# 5_Power_DWIN.net
KiCad netlist of a schematic drawn in Altium Designer
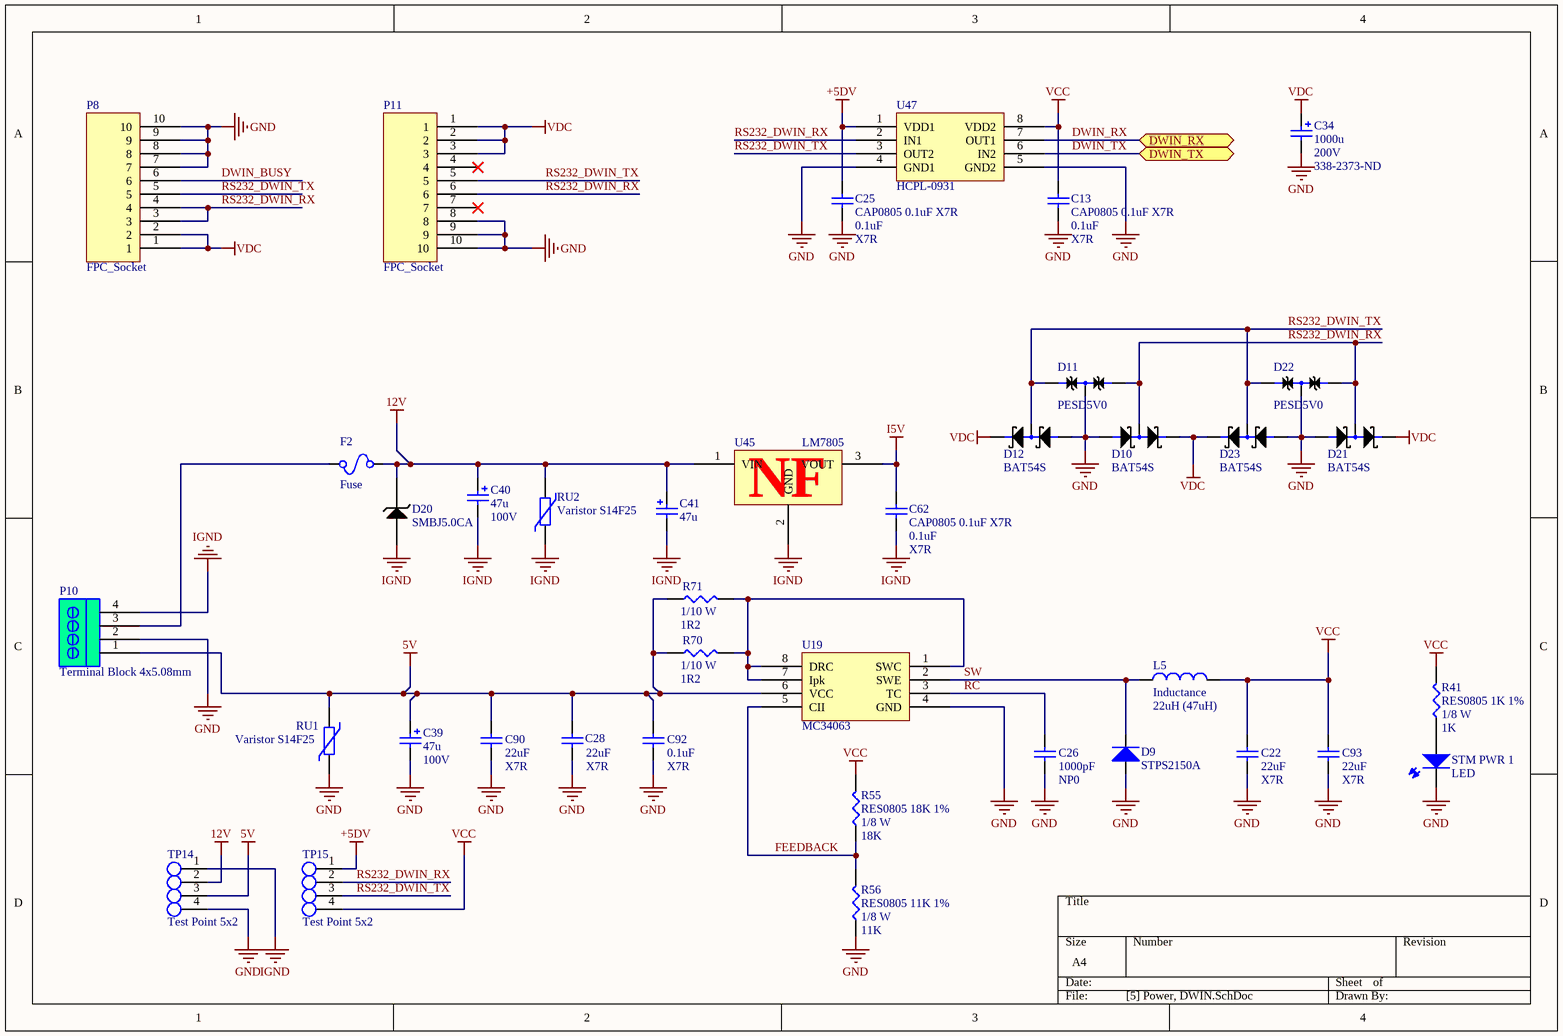
[diagram p0: [5] Power, DWIN.SchDoc]

(export (version "E")
  (design (tool "Eeschema 10.0.6"))
  (components
    (comp (ref "C13")
      (value "CAP0805 0.1uF X7R")
      (footprint "CAP0805")
      (description "Surface-mount ceramic multilayer capacitor")
      (fields
        (field (name "VOLTAGE") "50V")
        (field (name "TOLERANCE") "5%")
        (field (name "ALTIUM_VALUE") "0.1uF")
        (field (name "TYPE") "X7R")
      )
      (libsource (lib "Capacitors") (part "CAP0805 0.1uF X7R"))
    )
    (comp (ref "C22")
      (value "22uF")
      (footprint "CAP1210")
      (description "Surface-mount ceramic multilayer capacitor")
      (fields (field (name "VOLTAGE") "25V") (field (name "TOLERANCE") "10%") (field (name "TYPE") "X7R"))
      (libsource (lib "Capacitors") (part "ChipCap 22uF X7R"))
    )
    (comp (ref "C25")
      (value "CAP0805 0.1uF X7R")
      (footprint "CAP0805")
      (description "Surface-mount ceramic multilayer capacitor")
      (fields
        (field (name "VOLTAGE") "50V")
        (field (name "TOLERANCE") "5%")
        (field (name "ALTIUM_VALUE") "0.1uF")
        (field (name "TYPE") "X7R")
      )
      (libsource (lib "Capacitors") (part "CAP0805 0.1uF X7R"))
    )
    (comp (ref "C26")
      (value "1000pF")
      (footprint "CAP0805")
      (description "Surface-mount ceramic multilayer capacitor")
      (fields (field (name "VOLTAGE") "50V") (field (name "TOLERANCE") "5%") (field (name "TYPE") "NP0"))
      (libsource (lib "Capacitors") (part "CAP0805 1000pF NP0"))
    )
    (comp (ref "C28")
      (value "22uF")
      (footprint "CAP1210")
      (description "Surface-mount ceramic multilayer capacitor")
      (fields (field (name "VOLTAGE") "25V") (field (name "TOLERANCE") "10%") (field (name "TYPE") "X7R"))
      (libsource (lib "Capacitors") (part "ChipCap 22uF X7R"))
    )
    (comp (ref "C34")
      (value "1000u")
      (footprint "CAPPR7.5-16x25_1")
      (description "Polarized Capacitor (Radial)")
      (fields
        (field (name "VOLTAGE") "200V")
        (field (name "SUPPLIER PART NUMBER 1") "338-2373-ND")
        (field (name "Comment") "Cap Pol 200/100")
      )
      (libsource (lib "Common Devices") (part "Cap Pol 200/100"))
    )
    (comp (ref "C39")
      (value "47u")
      (footprint "CAPPR5-10x17_1")
      (description "Polarized Capacitor (Radial)")
      (fields (field (name "VOLTAGE") "100V") (field (name "Comment") "Cap Pol 100/47"))
      (libsource (lib "Common Devices") (part "Cap Pol 100/47"))
    )
    (comp (ref "C40")
      (value "47u")
      (footprint "CAPPR5-10x17_1")
      (description "Polarized Capacitor (Radial)")
      (fields (field (name "VOLTAGE") "100V") (field (name "Comment") "Cap Pol 100/47"))
      (libsource (lib "Common Devices") (part "Cap Pol 100/47"))
    )
    (comp (ref "C41")
      (value "47u")
      (footprint "CAPC7343")
      (description "Polarized Capacitor (Radial)")
      (fields (field (name "Comment") "Cap Pol SMD"))
      (libsource (lib "Common Devices") (part "Cap Pol Chip"))
    )
    (comp (ref "C62")
      (value "CAP0805 0.1uF X7R")
      (footprint "CAP0805")
      (description "Surface-mount ceramic multilayer capacitor")
      (fields
        (field (name "VOLTAGE") "50V")
        (field (name "TOLERANCE") "5%")
        (field (name "ALTIUM_VALUE") "0.1uF")
        (field (name "TYPE") "X7R")
      )
      (libsource (lib "Capacitors") (part "CAP0805 0.1uF X7R"))
    )
    (comp (ref "C90")
      (value "22uF")
      (footprint "CAP1210")
      (description "Surface-mount ceramic multilayer capacitor")
      (fields (field (name "VOLTAGE") "25V") (field (name "TOLERANCE") "10%") (field (name "TYPE") "X7R"))
      (libsource (lib "Capacitors") (part "ChipCap 22uF X7R"))
    )
    (comp (ref "C92")
      (value "0.1uF")
      (footprint "CAP0603")
      (description "Surface-mount ceramic multilayer capacitor")
      (fields (field (name "VOLTAGE") "100V") (field (name "TOLERANCE") "10%") (field (name "TYPE") "X7R"))
      (libsource (lib "Capacitors") (part "ChipCap 0.1uF X7R"))
    )
    (comp (ref "C93")
      (value "22uF")
      (footprint "CAP1210")
      (description "Surface-mount ceramic multilayer capacitor")
      (fields (field (name "VOLTAGE") "25V") (field (name "TOLERANCE") "10%") (field (name "TYPE") "X7R"))
      (libsource (lib "Capacitors") (part "ChipCap 22uF X7R"))
    )
    (comp (ref "D9")
      (value "STPS2150A")
      (footprint "DO-214AS")
      (description "Schottky diode")
      (fields (field (name "VOLTAGE") "150V") (field (name "MANUFACTURER") "ST"))
      (libsource (lib "Common Devices") (part "STPS2150A"))
    )
    (comp (ref "D10")
      (value "BAT54S")
      (footprint "SOT23")
      (description "Small signal schottky dual diode")
      (fields (field (name "MANUFACTURER PART NUMBER") "BAT54S-V-GS08") (field (name "VOLTAGE") "30"))
      (libsource (lib "") (part "BAT54S_1"))
    )
    (comp (ref "D11")
      (value "PESD5V0")
      (footprint "SOT23")
      (description "Low capacitance bidirectional double ESD protection diode")
      (fields (field (name "MANUFACTURER PART NUMBER") "PESD5V0S2BT.215") (field (name "VOLTAGE") "5V"))
      (libsource (lib "Protection") (part "PESD5V0"))
    )
    (comp (ref "D12")
      (value "BAT54S")
      (footprint "SOT23")
      (description "Small signal schottky dual diode")
      (fields (field (name "MANUFACTURER PART NUMBER") "BAT54S-V-GS08") (field (name "VOLTAGE") "30"))
      (libsource (lib "Protection") (part "BAT54S"))
    )
    (comp (ref "D20")
      (value "SMBJ5.0CA")
      (footprint "DO-214AS")
      (description "Transient Voltage Suppressor 600W uni-directional")
      (fields (field (name "VOLTAGE") "5.0V"))
      (libsource (lib "Protection") (part "SMBJ5.0CA"))
    )
    (comp (ref "D21")
      (value "BAT54S")
      (footprint "SOT23")
      (description "Small signal schottky dual diode")
      (fields (field (name "MANUFACTURER PART NUMBER") "BAT54S-V-GS08") (field (name "VOLTAGE") "30"))
      (libsource (lib "") (part "BAT54S_1"))
    )
    (comp (ref "D22")
      (value "PESD5V0")
      (footprint "SOT23")
      (description "Low capacitance bidirectional double ESD protection diode")
      (fields (field (name "MANUFACTURER PART NUMBER") "PESD5V0S2BT.215") (field (name "VOLTAGE") "5V"))
      (libsource (lib "Protection") (part "PESD5V0"))
    )
    (comp (ref "D23")
      (value "BAT54S")
      (footprint "SOT23")
      (description "Small signal schottky dual diode")
      (fields (field (name "MANUFACTURER PART NUMBER") "BAT54S-V-GS08") (field (name "VOLTAGE") "30"))
      (libsource (lib "Protection") (part "BAT54S"))
    )
    (comp (ref "F2")
      (value "Fuse")
      (footprint "PTC1812")
      (description "Fuse PTC 1812 Thermoresistor")
      (libsource (lib "Protection") (part "Fuse PTC1812"))
    )
    (comp (ref "L5")
      (value "Inductance")
      (footprint "IHPL-3232")
      (fields (field (name "ALTIUM_VALUE") "22uH (47uH)"))
      (libsource (lib "Common Devices") (part "ChipInductance"))
    )
    (comp (ref "P8")
      (value "FPC_Socket")
      (footprint "MOLEX Header 8 2mm Pitch")
      (libsource (lib "") (part "FPC_Socket_1"))
    )
    (comp (ref "P10")
      (value "Terminal Block 4x5.08mm")
      (footprint "Socket 4x5.08")
      (description "Terminal Block Socket Right Angle 4x5.08mm 2-Wall")
      (libsource (lib "IndustrialConnectors") (part "Socket_4x5.08_RA_2Wall"))
    )
    (comp (ref "P11")
      (value "FPC_Socket")
      (footprint "Molex FPC/FFC 10pin")
      (libsource (lib "RibbonConnectors") (part "FPC_Socket"))
    )
    (comp (ref "R41")
      (value "RES0805 1K 1%")
      (footprint "RES0805")
      (description "Think Film Chip resistor")
      (fields
        (field (name "TOLERANCE") "1%")
        (field (name "MANUFACTURER PART NUMBER") "RC0805FR-071KL")
        (field (name "RATING") "1/8 W")
        (field (name "ALTIUM_VALUE") "1K")
      )
      (libsource (lib "Resistors") (part "RES0805 1K 1%"))
    )
    (comp (ref "R55")
      (value "RES0805 18K 1%")
      (footprint "RES0805")
      (description "Think Film Chip resistor")
      (fields
        (field (name "TOLERANCE") "1%")
        (field (name "MANUFACTURER PART NUMBER") "RC0805FR-0718KL")
        (field (name "RATING") "1/8 W")
        (field (name "ALTIUM_VALUE") "18K")
      )
      (libsource (lib "Resistors") (part "RES0805 18K 1%"))
    )
    (comp (ref "R56")
      (value "RES0805 11K 1%")
      (footprint "RES0805")
      (description "Think Film Chip resistor")
      (fields
        (field (name "TOLERANCE") "1%")
        (field (name "MANUFACTURER PART NUMBER") "RC0805FR-0711KL")
        (field (name "RATING") "1/8 W")
        (field (name "ALTIUM_VALUE") "11K")
      )
      (libsource (lib "Resistors") (part "RES0805 11K 1%"))
    )
    (comp (ref "R70")
      (value "1R2")
      (footprint "RES1206")
      (description "Think Film Chip resistor")
      (fields
        (field (name "TOLERANCE") "1%")
        (field (name "RATING") "1/10 W")
        (field (name "Comment") "ChipRes 1R2 1%")
      )
      (libsource (lib "Resistors") (part "ChipRes 1R2 1%"))
    )
    (comp (ref "R71")
      (value "1R2")
      (footprint "RES1206")
      (description "Think Film Chip resistor")
      (fields
        (field (name "TOLERANCE") "1%")
        (field (name "RATING") "1/10 W")
        (field (name "Comment") "ChipRes 1R2 1%")
      )
      (libsource (lib "Resistors") (part "ChipRes 1R2 1%"))
    )
    (comp (ref "RU1")
      (value "Varistor S14F25")
      (footprint "S14K25")
      (description "varistor")
      (libsource (lib "Protection") (part "Varistor S14K25"))
    )
    (comp (ref "RU2")
      (value "Varistor S14F25")
      (footprint "S14K25")
      (description "varistor")
      (libsource (lib "Protection") (part "Varistor S14K25"))
    )
    (comp (ref "STM PWR 1") (value "LED") (footprint "PLCC-2") (libsource (lib "LEDs") (part "LED0603")))
    (comp (ref "TP14")
      (value "Test Point 5x2")
      (footprint "PG-1.5-13.5-4P-2.54PH")
      (libsource (lib "Connectors") (part "PG-1.5-13.5-4P-2.54PH"))
    )
    (comp (ref "TP15")
      (value "Test Point 5x2")
      (footprint "PG-1.5-13.5-4P-2.54PH")
      (libsource (lib "Connectors") (part "PG-1.5-13.5-4P-2.54PH"))
    )
    (comp (ref "U19")
      (value "MC34063")
      (footprint "SOP8")
      (description "DC/DC converter control circuit")
      (libsource (lib "ST ARM32") (part "MC34063"))
    )
    (comp (ref "U45")
      (value "LM7805")
      (footprint "TO-220")
      (description "Linear voltage regulator 1A")
      (libsource (lib "Fairchild") (part "LM7805"))
    )
    (comp (ref "U47")
      (value "HCPL-0931")
      (footprint "SOIC8")
      (description "2-bit bi-direction optoisolated buffer")
      (libsource (lib "AVAGO bi-direction optoisolated buffer") (part "HCPL-0931-000E"))
    )
  )
  (nets
    (net (code "1") (name "+5DV") (class "Default")
      (node (ref "C25") (pin "2") (pinfunction "2_2") (pintype "passive"))
      (node (ref "TP15") (pin "1") (pinfunction "1_1") (pintype "passive"))
      (node (ref "U47") (pin "1") (pinfunction "VDD1_1") (pintype "passive"))
    )
    (net (code "2") (name "/DWIN_BUSY") (class "Default")
      (node (ref "P8") (pin "6") (pinfunction "6_6") (pintype "passive"))
    )
    (net (code "3") (name "/DWIN_RX") (class "Default")
      (node (ref "U47") (pin "7") (pinfunction "OUT1_7") (pintype "passive"))
    )
    (net (code "4") (name "/DWIN_TX") (class "Default")
      (node (ref "U47") (pin "6") (pinfunction "IN2_6") (pintype "passive"))
    )
    (net (code "5") (name "/FEEDBACK") (class "Default")
      (node (ref "R55") (pin "1") (pintype "passive"))
      (node (ref "R56") (pin "2") (pintype "passive"))
      (node (ref "U19") (pin "5") (pinfunction "CII_5") (pintype "passive"))
    )
    (net (code "6") (name "/RC") (class "Default")
      (node (ref "C26") (pin "2") (pinfunction "2_2") (pintype "passive"))
      (node (ref "U19") (pin "3") (pinfunction "TC_3") (pintype "passive"))
    )
    (net (code "7") (name "/RS232_DWIN_RX") (class "Default")
      (node (ref "D10") (pin "3") (pinfunction "3_3") (pintype "passive"))
      (node (ref "D11") (pin "2") (pinfunction "2_2") (pintype "passive"))
      (node (ref "D21") (pin "3") (pinfunction "3_3") (pintype "passive"))
      (node (ref "D22") (pin "2") (pinfunction "2_2") (pintype "passive"))
      (node (ref "P11") (pin "6") (pinfunction "6_6") (pintype "passive"))
      (node (ref "P8") (pin "3") (pinfunction "3_3") (pintype "passive"))
      (node (ref "P8") (pin "4") (pinfunction "4_4") (pintype "passive"))
      (node (ref "TP15") (pin "2") (pinfunction "2_2") (pintype "passive"))
      (node (ref "U47") (pin "2") (pinfunction "IN1_2") (pintype "passive"))
    )
    (net (code "8") (name "/RS232_DWIN_TX") (class "Default")
      (node (ref "D11") (pin "1") (pinfunction "1_1") (pintype "passive"))
      (node (ref "D12") (pin "3") (pinfunction "3_3") (pintype "passive"))
      (node (ref "D22") (pin "1") (pinfunction "1_1") (pintype "passive"))
      (node (ref "D23") (pin "3") (pinfunction "3_3") (pintype "passive"))
      (node (ref "P11") (pin "5") (pinfunction "5_5") (pintype "passive"))
      (node (ref "P8") (pin "5") (pinfunction "5_5") (pintype "passive"))
      (node (ref "TP15") (pin "3") (pinfunction "3_3") (pintype "passive"))
      (node (ref "U47") (pin "3") (pinfunction "OUT2_3") (pintype "passive"))
    )
    (net (code "9") (name "/SW") (class "Default")
      (node (ref "D9") (pin "2") (pinfunction "K_2") (pintype "passive"))
      (node (ref "L5") (pin "2") (pintype "passive"))
      (node (ref "U19") (pin "2") (pinfunction "SWE_2") (pintype "passive"))
    )
    (net (code "10") (name "5V") (class "Default")
      (node (ref "C28") (pin "2") (pinfunction "2_2") (pintype "passive"))
      (node (ref "C39") (pin "1") (pinfunction "1_1") (pintype "passive"))
      (node (ref "C90") (pin "2") (pinfunction "2_2") (pintype "passive"))
      (node (ref "C92") (pin "2") (pinfunction "2_2") (pintype "passive"))
      (node (ref "P10") (pin "1") (pintype "passive"))
      (node (ref "R70") (pin "1") (pintype "passive"))
      (node (ref "R71") (pin "1") (pintype "passive"))
      (node (ref "RU1") (pin "2") (pinfunction "2_2") (pintype "passive"))
      (node (ref "TP14") (pin "3") (pinfunction "3_3") (pintype "passive"))
      (node (ref "U19") (pin "6") (pinfunction "VCC_6") (pintype "passive"))
    )
    (net (code "11") (name "12V") (class "Default")
      (node (ref "C40") (pin "1") (pinfunction "1_1") (pintype "passive"))
      (node (ref "C41") (pin "1") (pinfunction "1_1") (pintype "passive"))
      (node (ref "D20") (pin "1") (pinfunction "1_1") (pintype "passive"))
      (node (ref "F2") (pin "1") (pinfunction "1_1") (pintype "passive"))
      (node (ref "RU2") (pin "2") (pinfunction "2_2") (pintype "passive"))
      (node (ref "TP14") (pin "2") (pinfunction "2_2") (pintype "passive"))
      (node (ref "U45") (pin "1") (pinfunction "VIN_1") (pintype "passive"))
    )
    (net (code "12") (name "GND") (class "Default")
      (node (ref "C13") (pin "1") (pinfunction "1_1") (pintype "passive"))
      (node (ref "C22") (pin "1") (pinfunction "1_1") (pintype "passive"))
      (node (ref "C25") (pin "1") (pinfunction "1_1") (pintype "passive"))
      (node (ref "C26") (pin "1") (pinfunction "1_1") (pintype "passive"))
      (node (ref "C28") (pin "1") (pinfunction "1_1") (pintype "passive"))
      (node (ref "C34") (pin "2") (pinfunction "2_2") (pintype "passive"))
      (node (ref "C39") (pin "2") (pinfunction "2_2") (pintype "passive"))
      (node (ref "C90") (pin "1") (pinfunction "1_1") (pintype "passive"))
      (node (ref "C92") (pin "1") (pinfunction "1_1") (pintype "passive"))
      (node (ref "C93") (pin "1") (pinfunction "1_1") (pintype "passive"))
      (node (ref "D10") (pin "1") (pinfunction "1_1") (pintype "passive"))
      (node (ref "D11") (pin "3") (pinfunction "3_3") (pintype "passive"))
      (node (ref "D12") (pin "1") (pinfunction "1_1") (pintype "passive"))
      (node (ref "D21") (pin "1") (pinfunction "1_1") (pintype "passive"))
      (node (ref "D22") (pin "3") (pinfunction "3_3") (pintype "passive"))
      (node (ref "D23") (pin "1") (pinfunction "1_1") (pintype "passive"))
      (node (ref "D9") (pin "1") (pinfunction "A_1") (pintype "passive"))
      (node (ref "P10") (pin "2") (pintype "passive"))
      (node (ref "P11") (pin "10") (pinfunction "10_10") (pintype "passive"))
      (node (ref "P11") (pin "8") (pinfunction "8_8") (pintype "passive"))
      (node (ref "P11") (pin "9") (pinfunction "9_9") (pintype "passive"))
      (node (ref "P8") (pin "10") (pinfunction "10_10") (pintype "passive"))
      (node (ref "P8") (pin "7") (pinfunction "7_7") (pintype "passive"))
      (node (ref "P8") (pin "8") (pinfunction "8_8") (pintype "passive"))
      (node (ref "P8") (pin "9") (pinfunction "9_9") (pintype "passive"))
      (node (ref "R56") (pin "1") (pintype "passive"))
      (node (ref "RU1") (pin "1") (pinfunction "1_1") (pintype "passive"))
      (node (ref "STM PWR 1") (pin "1") (pinfunction "1_1") (pintype "passive"))
      (node (ref "TP14") (pin "4") (pinfunction "4_4") (pintype "passive"))
      (node (ref "U19") (pin "4") (pinfunction "GND_4") (pintype "passive"))
      (node (ref "U47") (pin "4") (pinfunction "GND1_4") (pintype "passive"))
      (node (ref "U47") (pin "5") (pinfunction "GND2_5") (pintype "passive"))
    )
    (net (code "13") (name "I5V") (class "Default")
      (node (ref "C62") (pin "2") (pinfunction "2_2") (pintype "passive"))
      (node (ref "U45") (pin "3") (pinfunction "VOUT_3") (pintype "passive"))
    )
    (net (code "14") (name "IGND") (class "Default")
      (node (ref "C40") (pin "2") (pinfunction "2_2") (pintype "passive"))
      (node (ref "C41") (pin "2") (pinfunction "2_2") (pintype "passive"))
      (node (ref "C62") (pin "1") (pinfunction "1_1") (pintype "passive"))
      (node (ref "D20") (pin "2") (pinfunction "2_2") (pintype "passive"))
      (node (ref "P10") (pin "4") (pintype "passive"))
      (node (ref "RU2") (pin "1") (pinfunction "1_1") (pintype "passive"))
      (node (ref "TP14") (pin "1") (pinfunction "1_1") (pintype "passive"))
      (node (ref "U45") (pin "2") (pinfunction "GND_2") (pintype "passive"))
    )
    (net (code "15") (name "Net-(F2-Pad2)") (class "Default")
      (node (ref "F2") (pin "2") (pinfunction "2_2") (pintype "passive"))
      (node (ref "P10") (pin "3") (pintype "passive"))
    )
    (net (code "16") (name "Net-(R41-Pad1)") (class "Default")
      (node (ref "R41") (pin "1") (pintype "passive"))
      (node (ref "STM PWR 1") (pin "2") (pinfunction "2_2") (pintype "passive"))
    )
    (net (code "17") (name "Net-(U19-DRC)") (class "Default")
      (node (ref "R70") (pin "2") (pintype "passive"))
      (node (ref "R71") (pin "2") (pintype "passive"))
      (node (ref "U19") (pin "1") (pinfunction "SWC_1") (pintype "passive"))
      (node (ref "U19") (pin "7") (pinfunction "Ipk_7") (pintype "passive"))
      (node (ref "U19") (pin "8") (pinfunction "DRC_8") (pintype "passive"))
    )
    (net (code "18") (name "VCC") (class "Default")
      (node (ref "C13") (pin "2") (pinfunction "2_2") (pintype "passive"))
      (node (ref "C22") (pin "2") (pinfunction "2_2") (pintype "passive"))
      (node (ref "C93") (pin "2") (pinfunction "2_2") (pintype "passive"))
      (node (ref "L5") (pin "1") (pintype "passive"))
      (node (ref "R41") (pin "2") (pintype "passive"))
      (node (ref "R55") (pin "2") (pintype "passive"))
      (node (ref "TP15") (pin "4") (pinfunction "4_4") (pintype "passive"))
      (node (ref "U47") (pin "8") (pinfunction "VDD2_8") (pintype "passive"))
    )
    (net (code "19") (name "VDC") (class "Default")
      (node (ref "C34") (pin "1") (pinfunction "1_1") (pintype "passive"))
      (node (ref "D10") (pin "2") (pinfunction "2_2") (pintype "passive"))
      (node (ref "D12") (pin "2") (pinfunction "2_2") (pintype "passive"))
      (node (ref "D21") (pin "2") (pinfunction "2_2") (pintype "passive"))
      (node (ref "D23") (pin "2") (pinfunction "2_2") (pintype "passive"))
      (node (ref "P11") (pin "1") (pinfunction "1_1") (pintype "passive"))
      (node (ref "P11") (pin "2") (pinfunction "2_2") (pintype "passive"))
      (node (ref "P11") (pin "3") (pinfunction "3_3") (pintype "passive"))
      (node (ref "P8") (pin "1") (pinfunction "1_1") (pintype "passive"))
      (node (ref "P8") (pin "2") (pinfunction "2_2") (pintype "passive"))
    )
    (net (code "20") (name "unconnected-(P11-Pad4)") (class "Default")
      (node (ref "P11") (pin "4") (pinfunction "4_4") (pintype "passive+no_connect"))
    )
    (net (code "21") (name "unconnected-(P11-Pad7)") (class "Default")
      (node (ref "P11") (pin "7") (pinfunction "7_7") (pintype "passive+no_connect"))
    )
  )
)
